# 3008_D_lkov.net
KiCad netlist of a schematic drawn in EAGLE
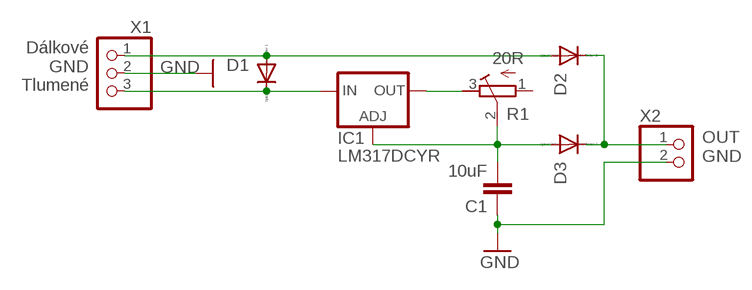
[diagram p0: schematic, sheet 1]

(export (version "E")
  (design (tool "Eeschema 10.0.6"))
  (components
    (comp (ref "C1")
      (value "10uF")
      (footprint "eagle-import:C1210")
      (libsource (lib "eagle-import") (part "C-EUC1210"))
    )
    (comp (ref "D1")
      (value "DIODE-DO214AA")
      (footprint "eagle-import:DO214AA")
      (libsource (lib "eagle-import") (part "DIODE-DO214AA"))
    )
    (comp (ref "D2")
      (value "DIODE-DO214AA")
      (footprint "eagle-import:DO214AA")
      (libsource (lib "eagle-import") (part "DIODE-DO214AA"))
    )
    (comp (ref "D3")
      (value "DIODE-DO214AA")
      (footprint "eagle-import:DO214AA")
      (libsource (lib "eagle-import") (part "DIODE-DO214AA"))
    )
    (comp (ref "IC1")
      (value "LM317DCYR")
      (footprint "eagle-import:SOT223")
      (libsource (lib "eagle-import") (part "LM317?MSTT3"))
    )
    (comp (ref "R1")
      (value "20R")
      (footprint "eagle-import:3362P")
      (libsource (lib "eagle-import") (part "R-TRIMM3362P"))
    )
    (comp (ref "X1")
      (value "PINHD-1X3")
      (footprint "eagle-import:1X03")
      (libsource (lib "eagle-import") (part "PINHD-1X3"))
    )
    (comp (ref "X2")
      (value "PINHD-1X2")
      (footprint "eagle-import:1X02")
      (libsource (lib "eagle-import") (part "PINHD-1X2"))
    )
  )
  (nets
    (net (code "1") (name "GND") (class "Default")
      (node (ref "C1") (pin "1") (pinfunction "1_1") (pintype "passive"))
      (node (ref "X1") (pin "2") (pinfunction "2_2") (pintype "passive"))
      (node (ref "X2") (pin "2") (pinfunction "2_2") (pintype "passive"))
    )
    (net (code "2") (name "Net-(D1-PadA)") (class "Default")
      (node (ref "D1") (pin "A") (pinfunction "A_A") (pintype "passive"))
      (node (ref "D2") (pin "A") (pinfunction "A_A") (pintype "passive"))
      (node (ref "X1") (pin "1") (pinfunction "1_1") (pintype "passive"))
    )
    (net (code "3") (name "Net-(D2-PadC)") (class "Default")
      (node (ref "D2") (pin "C") (pinfunction "C_C") (pintype "passive"))
      (node (ref "D3") (pin "C") (pinfunction "C_C") (pintype "passive"))
      (node (ref "X2") (pin "1") (pinfunction "1_1") (pintype "passive"))
    )
    (net (code "4") (name "Net-(IC1-ADJ)") (class "Default")
      (node (ref "C1") (pin "2") (pinfunction "2_2") (pintype "passive"))
      (node (ref "D3") (pin "A") (pinfunction "A_A") (pintype "passive"))
      (node (ref "IC1") (pin "1") (pinfunction "ADJ_1") (pintype "input"))
      (node (ref "R1") (pin "2") (pinfunction "S_2") (pintype "passive"))
    )
    (net (code "5") (name "Net-(IC1-IN)") (class "Default")
      (node (ref "D1") (pin "C") (pinfunction "C_C") (pintype "passive"))
      (node (ref "IC1") (pin "3") (pinfunction "IN_3") (pintype "input"))
      (node (ref "X1") (pin "3") (pinfunction "3_3") (pintype "passive"))
    )
    (net (code "6") (name "Net-(R1-E)") (class "Default")
      (node (ref "IC1") (pin "2") (pinfunction "OUT_2") (pintype "passive"))
      (node (ref "IC1") (pin "4") (pinfunction "OUT_4") (pintype "passive"))
      (node (ref "R1") (pin "3") (pinfunction "E_3") (pintype "passive"))
    )
    (net (code "7") (name "unconnected-(R1-A-Pad1)") (class "Default")
      (node (ref "R1") (pin "1") (pinfunction "A_1") (pintype "passive"))
    )
  )
)
